# CAN.net
KiCad netlist of a schematic drawn in Altium Designer
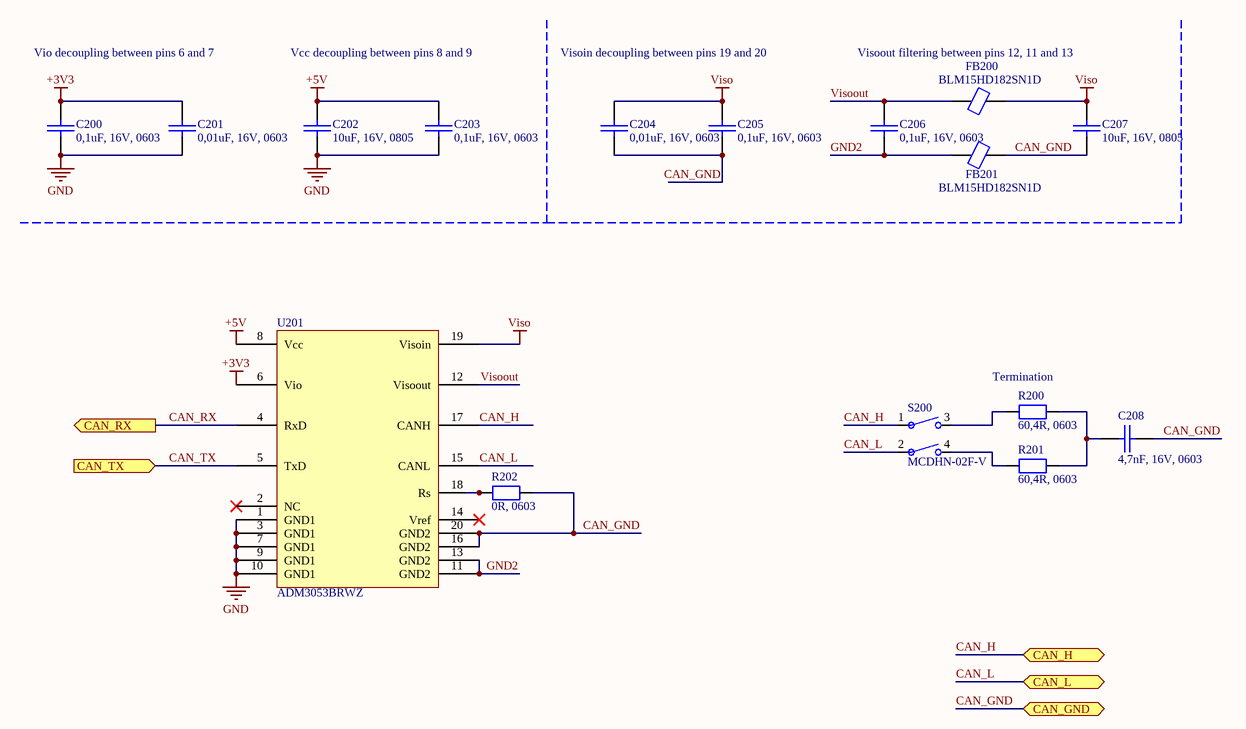
[diagram p0: CAN.SchDoc]

(export (version "E")
  (design (tool "Eeschema 10.0.6"))
  (components
    (comp (ref "C200")
      (value "0,1uF, 16V, 0603")
      (footprint "CAP [0603] 1608")
      (description "Default capacitor part")
      (libsource (lib "Formula Student Team Tallinn (Estonia)") (part "Capacitor"))
    )
    (comp (ref "C201")
      (value "0,01uF, 16V, 0603")
      (footprint "CAP [0603] 1608")
      (description "Default capacitor part")
      (libsource (lib "Formula Student Team Tallinn (Estonia)") (part "Capacitor"))
    )
    (comp (ref "C202")
      (value "10uF, 16V, 0805")
      (footprint "CAP [0805] 2012")
      (description "Default capacitor part")
      (libsource (lib "Formula Student Team Tallinn (Estonia)") (part "Capacitor"))
    )
    (comp (ref "C203")
      (value "0,1uF, 16V, 0603")
      (footprint "CAP [0603] 1608")
      (description "Default capacitor part")
      (libsource (lib "Formula Student Team Tallinn (Estonia)") (part "Capacitor"))
    )
    (comp (ref "C204")
      (value "0,01uF, 16V, 0603")
      (footprint "CAP [0603] 1608")
      (description "Default capacitor part")
      (libsource (lib "Formula Student Team Tallinn (Estonia)") (part "Capacitor"))
    )
    (comp (ref "C205")
      (value "0,1uF, 16V, 0603")
      (footprint "CAP [0603] 1608")
      (description "Default capacitor part")
      (libsource (lib "Formula Student Team Tallinn (Estonia)") (part "Capacitor"))
    )
    (comp (ref "C206")
      (value "0,1uF, 16V, 0603")
      (footprint "CAP [0603] 1608")
      (description "Default capacitor part")
      (libsource (lib "Formula Student Team Tallinn (Estonia)") (part "Capacitor"))
    )
    (comp (ref "C207")
      (value "10uF, 16V, 0805")
      (footprint "CAP [0805] 2012")
      (description "Default capacitor part")
      (libsource (lib "Formula Student Team Tallinn (Estonia)") (part "Capacitor"))
    )
    (comp (ref "C208")
      (value "4,7nF, 16V, 0603")
      (footprint "CAP [0603] 1608")
      (description "Default capacitor part")
      (libsource (lib "Formula Student Team Tallinn (Estonia)") (part "Capacitor"))
    )
    (comp (ref "FB200")
      (value "BLM15HD182SN1D")
      (footprint "IND [0402] 1005")
      (description "Ferrite Chip, 1 Function(s), 0.2A, 2 Pin(s)")
      (fields (field (name "MANUFACTURER") "Murata"))
      (libsource (lib "Formula Student Team Tallinn (Estonia)") (part "Ferrite Bead"))
    )
    (comp (ref "FB201")
      (value "BLM15HD182SN1D")
      (footprint "IND [0402] 1005")
      (description "Ferrite Chip, 1 Function(s), 0.2A, 2 Pin(s)")
      (fields (field (name "MANUFACTURER") "Murata"))
      (libsource (lib "Formula Student Team Tallinn (Estonia)") (part "Ferrite Bead"))
    )
    (comp (ref "R200")
      (value "60,4R, 0603")
      (footprint "RES [0603] 1608")
      (description "Standard resistor part")
      (libsource (lib "Formula Student Team Tallinn (Estonia)") (part "Resistor"))
    )
    (comp (ref "R201")
      (value "60,4R, 0603")
      (footprint "RES [0603] 1608")
      (description "Standard resistor part")
      (libsource (lib "Formula Student Team Tallinn (Estonia)") (part "Resistor"))
    )
    (comp (ref "R202")
      (value "0R, 0603")
      (footprint "RES [0603] 1608")
      (description "Standard resistor part")
      (libsource (lib "Formula Student Team Tallinn (Estonia)") (part "Resistor"))
    )
    (comp (ref "S200")
      (value "MCDHN-02F-V")
      (footprint "MCDHN-02F-V-Footprint-1")
      (fields (field (name "MANUFACTURER") "Multicomp Pro"))
      (libsource (lib "Formula Student Team Tallinn (Estonia)") (part "Double DIP Switch"))
    )
    (comp (ref "U201")
      (value "ADM3053BRWZ")
      (footprint "SOIC-20")
      (description "Interface Circuit, 1-Trnsvr, PDSO20")
      (fields (field (name "MANUFACTURER") "Analog Devices"))
      (libsource (lib "Formula Student Team Tallinn (Estonia)") (part "CAN Tranciever{colon} Isolated"))
    )
  )
  (nets
    (net (code "1") (name "+3V3") (class "Default")
      (node (ref "C200") (pin "1") (pinfunction "1_1") (pintype "passive"))
      (node (ref "C201") (pin "1") (pinfunction "1_1") (pintype "passive"))
      (node (ref "U201") (pin "6") (pinfunction "Vio_6") (pintype "passive"))
    )
    (net (code "2") (name "+5V") (class "Default")
      (node (ref "C202") (pin "1") (pinfunction "1_1") (pintype "passive"))
      (node (ref "C203") (pin "1") (pinfunction "1_1") (pintype "passive"))
      (node (ref "U201") (pin "8") (pinfunction "Vcc_8") (pintype "passive"))
    )
    (net (code "3") (name "/CAN_GND") (class "Default")
      (node (ref "C204") (pin "2") (pinfunction "2_2") (pintype "passive"))
      (node (ref "C205") (pin "2") (pinfunction "2_2") (pintype "passive"))
      (node (ref "C207") (pin "2") (pinfunction "2_2") (pintype "passive"))
      (node (ref "C208") (pin "2") (pinfunction "2_2") (pintype "passive"))
      (node (ref "FB201") (pin "2") (pinfunction "2_2") (pintype "passive"))
      (node (ref "R202") (pin "1") (pinfunction "1_1") (pintype "passive"))
      (node (ref "U201") (pin "16") (pinfunction "GND2_16") (pintype "passive"))
      (node (ref "U201") (pin "20") (pinfunction "GND2_20") (pintype "passive"))
    )
    (net (code "4") (name "/CAN_H") (class "Default")
      (node (ref "S200") (pin "1") (pinfunction "1_1") (pintype "passive"))
      (node (ref "U201") (pin "17") (pinfunction "CANH_17") (pintype "passive"))
    )
    (net (code "5") (name "/CAN_L") (class "Default")
      (node (ref "S200") (pin "2") (pinfunction "2_2") (pintype "passive"))
      (node (ref "U201") (pin "15") (pinfunction "CANL_15") (pintype "passive"))
    )
    (net (code "6") (name "/CAN_RX") (class "Default")
      (node (ref "U201") (pin "4") (pinfunction "RxD_4") (pintype "passive"))
    )
    (net (code "7") (name "/CAN_TX") (class "Default")
      (node (ref "U201") (pin "5") (pinfunction "TxD_5") (pintype "passive"))
    )
    (net (code "8") (name "/GND2") (class "Default")
      (node (ref "C206") (pin "2") (pinfunction "2_2") (pintype "passive"))
      (node (ref "FB201") (pin "1") (pinfunction "1_1") (pintype "passive"))
      (node (ref "U201") (pin "11") (pinfunction "GND2_11") (pintype "passive"))
      (node (ref "U201") (pin "13") (pinfunction "GND2_13") (pintype "passive"))
    )
    (net (code "9") (name "/Visoout") (class "Default")
      (node (ref "C206") (pin "1") (pinfunction "1_1") (pintype "passive"))
      (node (ref "FB200") (pin "1") (pinfunction "1_1") (pintype "passive"))
      (node (ref "U201") (pin "12") (pinfunction "Visoout_12") (pintype "passive"))
    )
    (net (code "10") (name "GND") (class "Default")
      (node (ref "C200") (pin "2") (pinfunction "2_2") (pintype "passive"))
      (node (ref "C201") (pin "2") (pinfunction "2_2") (pintype "passive"))
      (node (ref "C202") (pin "2") (pinfunction "2_2") (pintype "passive"))
      (node (ref "C203") (pin "2") (pinfunction "2_2") (pintype "passive"))
      (node (ref "U201") (pin "1") (pinfunction "GND1_1") (pintype "passive"))
      (node (ref "U201") (pin "10") (pinfunction "GND1_10") (pintype "passive"))
      (node (ref "U201") (pin "3") (pinfunction "GND1_3") (pintype "passive"))
      (node (ref "U201") (pin "7") (pinfunction "GND1_7") (pintype "passive"))
      (node (ref "U201") (pin "9") (pinfunction "GND1_9") (pintype "passive"))
    )
    (net (code "11") (name "Net-(C208-Pad1)") (class "Default")
      (node (ref "C208") (pin "1") (pinfunction "1_1") (pintype "passive"))
      (node (ref "R200") (pin "1") (pinfunction "1_1") (pintype "passive"))
      (node (ref "R201") (pin "1") (pinfunction "1_1") (pintype "passive"))
    )
    (net (code "12") (name "Net-(R200-Pad2)") (class "Default")
      (node (ref "R200") (pin "2") (pinfunction "2_2") (pintype "passive"))
      (node (ref "S200") (pin "3") (pinfunction "3_3") (pintype "passive"))
    )
    (net (code "13") (name "Net-(R201-Pad2)") (class "Default")
      (node (ref "R201") (pin "2") (pinfunction "2_2") (pintype "passive"))
      (node (ref "S200") (pin "4") (pinfunction "4_4") (pintype "passive"))
    )
    (net (code "14") (name "Net-(U201-Rs)") (class "Default")
      (node (ref "R202") (pin "2") (pinfunction "2_2") (pintype "passive"))
      (node (ref "U201") (pin "18") (pinfunction "Rs_18") (pintype "passive"))
    )
    (net (code "15") (name "Viso") (class "Default")
      (node (ref "C204") (pin "1") (pinfunction "1_1") (pintype "passive"))
      (node (ref "C205") (pin "1") (pinfunction "1_1") (pintype "passive"))
      (node (ref "C207") (pin "1") (pinfunction "1_1") (pintype "passive"))
      (node (ref "FB200") (pin "2") (pinfunction "2_2") (pintype "passive"))
      (node (ref "U201") (pin "19") (pinfunction "Visoin_19") (pintype "passive"))
    )
    (net (code "16") (name "unconnected-(U201-NC-Pad2)") (class "Default")
      (node (ref "U201") (pin "2") (pinfunction "NC_2") (pintype "passive+no_connect"))
    )
    (net (code "17") (name "unconnected-(U201-Vref-Pad14)") (class "Default")
      (node (ref "U201") (pin "14") (pinfunction "Vref_14") (pintype "passive+no_connect"))
    )
  )
)
